# TLF01.net
KiCad netlist of a schematic drawn in EAGLE
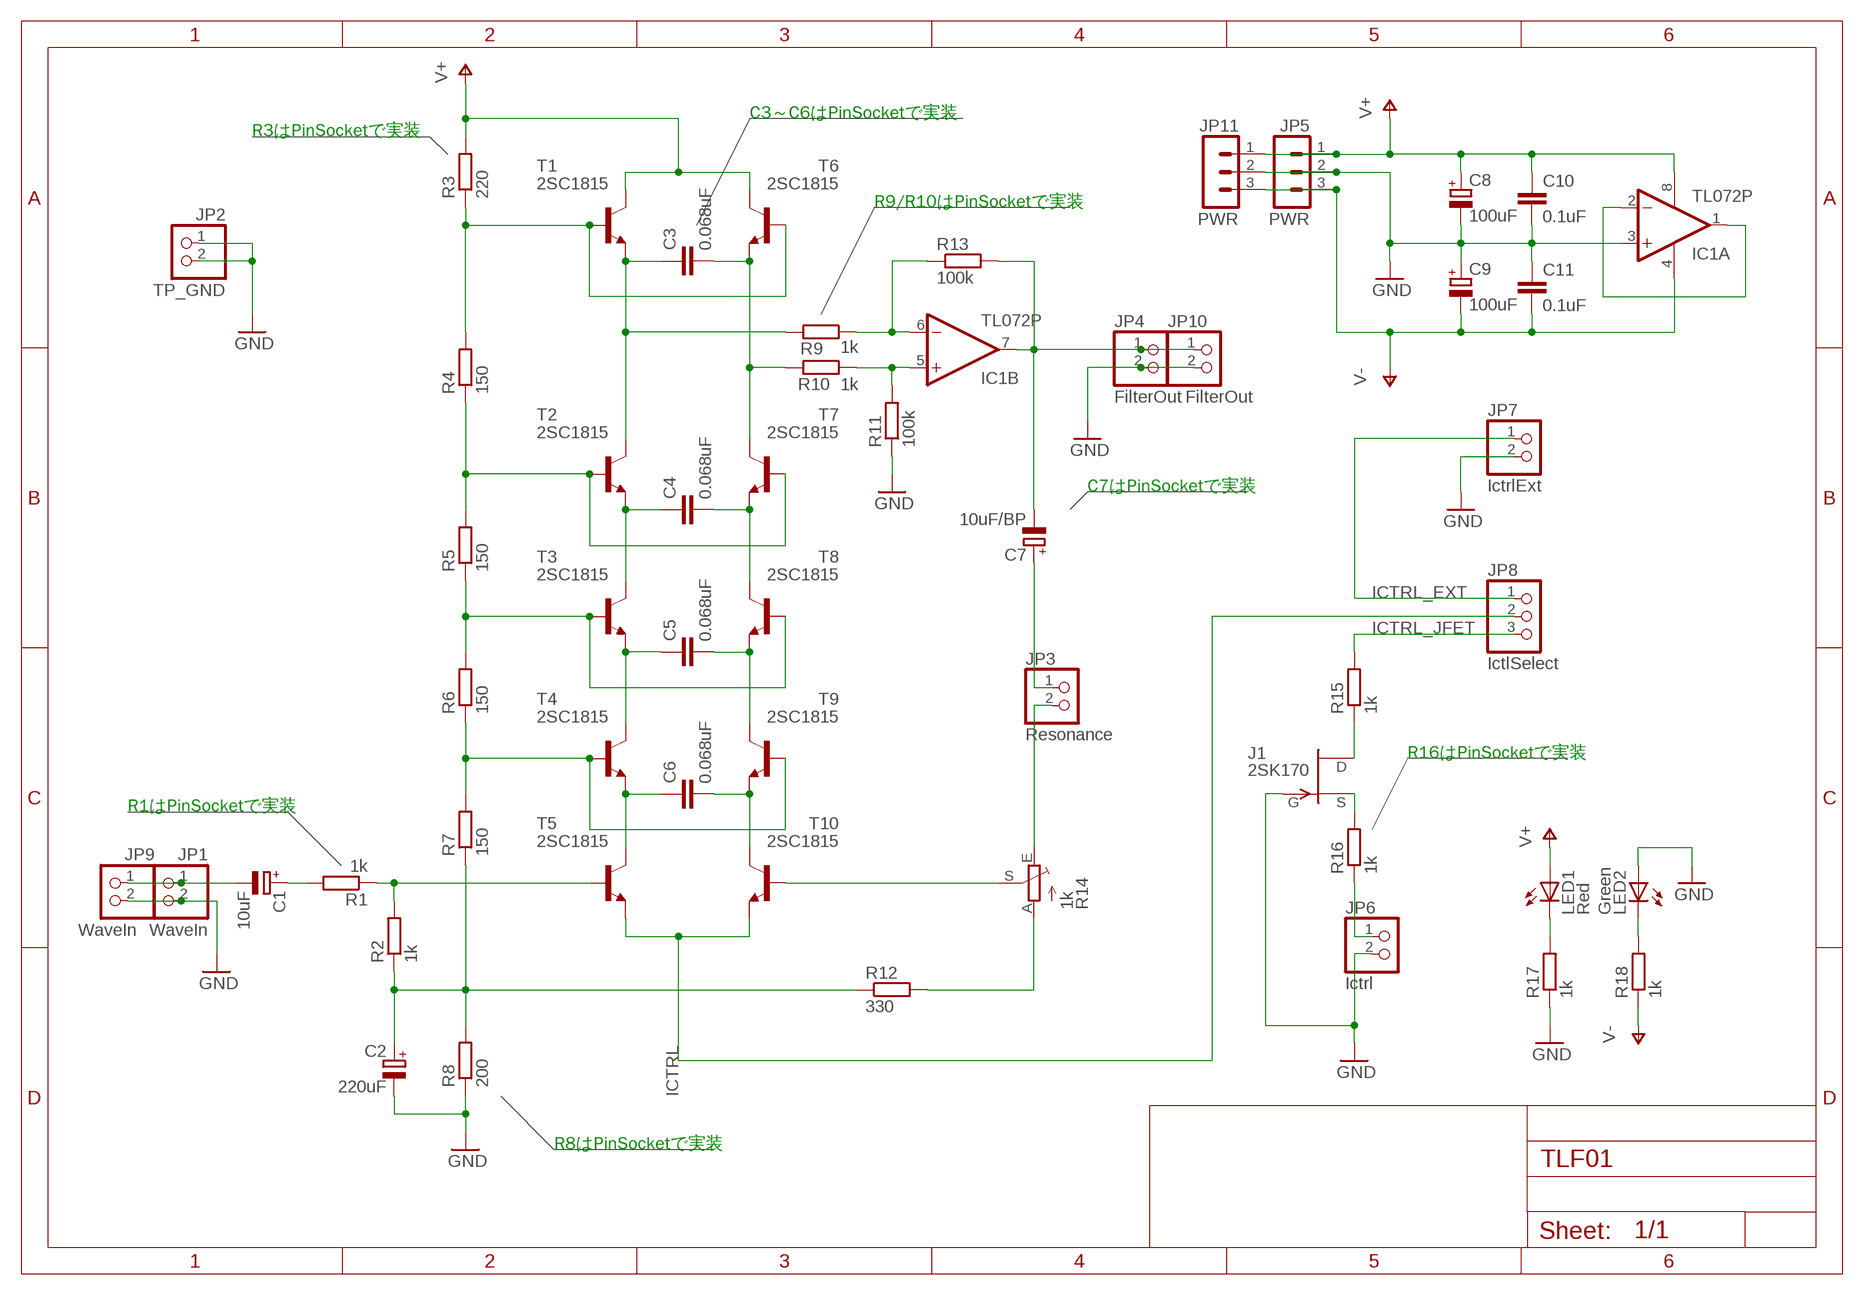
[diagram p0: schematic, sheet 1]

(export (version "E")
  (design (tool "Eeschema 10.0.6"))
  (components
    (comp (ref "C1")
      (value "10uF")
      (footprint "eagle-import:E2,5-6")
      (libsource (lib "eagle-import") (part "CPOL-EUE2.5-6"))
    )
    (comp (ref "C2")
      (value "220uF")
      (footprint "eagle-import:E5-8,5")
      (libsource (lib "eagle-import") (part "CPOL-EUE5-8.5"))
    )
    (comp (ref "C3")
      (value "0.068uF")
      (footprint "eagle-import:C075-052X106")
      (libsource (lib "eagle-import") (part "C-EU075-052X106"))
    )
    (comp (ref "C4")
      (value "0.068uF")
      (footprint "eagle-import:C075-052X106")
      (libsource (lib "eagle-import") (part "C-EU075-052X106"))
    )
    (comp (ref "C5")
      (value "0.068uF")
      (footprint "eagle-import:C075-052X106")
      (libsource (lib "eagle-import") (part "C-EU075-052X106"))
    )
    (comp (ref "C6")
      (value "0.068uF")
      (footprint "eagle-import:C075-052X106")
      (libsource (lib "eagle-import") (part "C-EU075-052X106"))
    )
    (comp (ref "C7")
      (value "10uF/BP")
      (footprint "eagle-import:E5-8,5")
      (libsource (lib "eagle-import") (part "CPOL-EUE5-8.5"))
    )
    (comp (ref "C8")
      (value "100uF")
      (footprint "eagle-import:E2,5-7")
      (libsource (lib "eagle-import") (part "CPOL-EUE2.5-7"))
    )
    (comp (ref "C9")
      (value "100uF")
      (footprint "eagle-import:E2,5-7")
      (libsource (lib "eagle-import") (part "CPOL-EUE2.5-7"))
    )
    (comp (ref "C10")
      (value "0.1uF")
      (footprint "eagle-import:C025-025X050")
      (libsource (lib "eagle-import") (part "C-EU025-025X050"))
    )
    (comp (ref "C11")
      (value "0.1uF")
      (footprint "eagle-import:C025-025X050")
      (libsource (lib "eagle-import") (part "C-EU025-025X050"))
    )
    (comp (ref "IC1")
      (value "TL072P")
      (footprint "eagle-import:DIL08")
      (libsource (lib "eagle-import") (part "TL072P"))
    )
    (comp (ref "J1")
      (value "2SK170")
      (footprint "eagle-import:TO-92")
      (libsource (lib "eagle-import") (part "2SK170"))
    )
    (comp (ref "JP1")
      (value "WaveIn")
      (footprint "eagle-import:1X02")
      (libsource (lib "eagle-import") (part "PINHD-1X2"))
    )
    (comp (ref "JP2")
      (value "TP_GND")
      (footprint "eagle-import:1X02")
      (libsource (lib "eagle-import") (part "PINHD-1X2"))
    )
    (comp (ref "JP3")
      (value "Resonance")
      (footprint "eagle-import:1X02")
      (libsource (lib "eagle-import") (part "PINHD-1X2"))
    )
    (comp (ref "JP4")
      (value "FilterOut")
      (footprint "eagle-import:1X02")
      (libsource (lib "eagle-import") (part "PINHD-1X2"))
    )
    (comp (ref "JP5")
      (value "PWR")
      (footprint "eagle-import:B3B-EH-A")
      (libsource (lib "eagle-import") (part "B3B-EH-A"))
    )
    (comp (ref "JP6")
      (value "Ictrl")
      (footprint "eagle-import:1X02")
      (libsource (lib "eagle-import") (part "PINHD-1X2"))
    )
    (comp (ref "JP7")
      (value "IctrlExt")
      (footprint "eagle-import:1X02")
      (libsource (lib "eagle-import") (part "PINHD-1X2"))
    )
    (comp (ref "JP8")
      (value "IctlSelect")
      (footprint "eagle-import:1X03")
      (libsource (lib "eagle-import") (part "PINHD-1X3"))
    )
    (comp (ref "JP9")
      (value "WaveIn")
      (footprint "eagle-import:1X02")
      (libsource (lib "eagle-import") (part "PINHD-1X2"))
    )
    (comp (ref "JP10")
      (value "FilterOut")
      (footprint "eagle-import:1X02")
      (libsource (lib "eagle-import") (part "PINHD-1X2"))
    )
    (comp (ref "JP11")
      (value "PWR")
      (footprint "eagle-import:B3B-EH-A")
      (libsource (lib "eagle-import") (part "B3B-EH-A"))
    )
    (comp (ref "LED1")
      (value "Red")
      (footprint "eagle-import:LED3MM")
      (libsource (lib "eagle-import") (part "LED3MM"))
    )
    (comp (ref "LED2")
      (value "Green")
      (footprint "eagle-import:LED3MM")
      (libsource (lib "eagle-import") (part "LED3MM"))
    )
    (comp (ref "R1")
      (value "1k")
      (footprint "eagle-import:0207_7")
      (libsource (lib "eagle-import") (part "R-EU_0207/7"))
    )
    (comp (ref "R2")
      (value "1k")
      (footprint "eagle-import:0207_7")
      (libsource (lib "eagle-import") (part "R-EU_0207/7"))
    )
    (comp (ref "R3")
      (value "220")
      (footprint "eagle-import:0207_7")
      (libsource (lib "eagle-import") (part "R-EU_0207/7"))
    )
    (comp (ref "R4")
      (value "150")
      (footprint "eagle-import:0207_7")
      (libsource (lib "eagle-import") (part "R-EU_0207/7"))
    )
    (comp (ref "R5")
      (value "150")
      (footprint "eagle-import:0207_7")
      (libsource (lib "eagle-import") (part "R-EU_0207/7"))
    )
    (comp (ref "R6")
      (value "150")
      (footprint "eagle-import:0207_7")
      (libsource (lib "eagle-import") (part "R-EU_0207/7"))
    )
    (comp (ref "R7")
      (value "150")
      (footprint "eagle-import:0207_7")
      (libsource (lib "eagle-import") (part "R-EU_0207/7"))
    )
    (comp (ref "R8")
      (value "200")
      (footprint "eagle-import:0207_7")
      (libsource (lib "eagle-import") (part "R-EU_0207/7"))
    )
    (comp (ref "R9")
      (value "1k")
      (footprint "eagle-import:0207_7")
      (libsource (lib "eagle-import") (part "R-EU_0207/7"))
    )
    (comp (ref "R10")
      (value "1k")
      (footprint "eagle-import:0207_7")
      (libsource (lib "eagle-import") (part "R-EU_0207/7"))
    )
    (comp (ref "R11")
      (value "100k")
      (footprint "eagle-import:0207_7")
      (libsource (lib "eagle-import") (part "R-EU_0207/7"))
    )
    (comp (ref "R12")
      (value "330")
      (footprint "eagle-import:0207_7")
      (libsource (lib "eagle-import") (part "R-EU_0207/7"))
    )
    (comp (ref "R13")
      (value "100k")
      (footprint "eagle-import:0207_7")
      (libsource (lib "eagle-import") (part "R-EU_0207/7"))
    )
    (comp (ref "R14")
      (value "1k")
      (footprint "eagle-import:B25P")
      (libsource (lib "eagle-import") (part "TRIM_EU-B25P"))
    )
    (comp (ref "R15")
      (value "1k")
      (footprint "eagle-import:0207_7")
      (libsource (lib "eagle-import") (part "R-EU_0207/7"))
    )
    (comp (ref "R16")
      (value "1k")
      (footprint "eagle-import:0207_7")
      (libsource (lib "eagle-import") (part "R-EU_0207/7"))
    )
    (comp (ref "R17")
      (value "1k")
      (footprint "eagle-import:0207_7")
      (libsource (lib "eagle-import") (part "R-EU_0207/7"))
    )
    (comp (ref "R18")
      (value "1k")
      (footprint "eagle-import:0207_7")
      (libsource (lib "eagle-import") (part "R-EU_0207/7"))
    )
    (comp (ref "T1")
      (value "2SC1815")
      (footprint "eagle-import:TO92-ECB")
      (libsource (lib "eagle-import") (part "-NPN-TO92-ECB"))
    )
    (comp (ref "T2")
      (value "2SC1815")
      (footprint "eagle-import:TO92-ECB")
      (libsource (lib "eagle-import") (part "-NPN-TO92-ECB"))
    )
    (comp (ref "T3")
      (value "2SC1815")
      (footprint "eagle-import:TO92-ECB")
      (libsource (lib "eagle-import") (part "-NPN-TO92-ECB"))
    )
    (comp (ref "T4")
      (value "2SC1815")
      (footprint "eagle-import:TO92-ECB")
      (libsource (lib "eagle-import") (part "-NPN-TO92-ECB"))
    )
    (comp (ref "T5")
      (value "2SC1815")
      (footprint "eagle-import:TO92-ECB")
      (libsource (lib "eagle-import") (part "-NPN-TO92-ECB"))
    )
    (comp (ref "T6")
      (value "2SC1815")
      (footprint "eagle-import:TO92-ECB")
      (libsource (lib "eagle-import") (part "-NPN-TO92-ECB"))
    )
    (comp (ref "T7")
      (value "2SC1815")
      (footprint "eagle-import:TO92-ECB")
      (libsource (lib "eagle-import") (part "-NPN-TO92-ECB"))
    )
    (comp (ref "T8")
      (value "2SC1815")
      (footprint "eagle-import:TO92-ECB")
      (libsource (lib "eagle-import") (part "-NPN-TO92-ECB"))
    )
    (comp (ref "T9")
      (value "2SC1815")
      (footprint "eagle-import:TO92-ECB")
      (libsource (lib "eagle-import") (part "-NPN-TO92-ECB"))
    )
    (comp (ref "T10")
      (value "2SC1815")
      (footprint "eagle-import:TO92-ECB")
      (libsource (lib "eagle-import") (part "-NPN-TO92-ECB"))
    )
  )
  (nets
    (net (code "1") (name "/ICTRL") (class "Default")
      (node (ref "JP8") (pin "2") (pinfunction "2_2") (pintype "passive"))
      (node (ref "T10") (pin "E") (pinfunction "E_E") (pintype "passive"))
      (node (ref "T5") (pin "E") (pinfunction "E_E") (pintype "passive"))
    )
    (net (code "2") (name "/ICTRL_EXT") (class "Default")
      (node (ref "JP7") (pin "1") (pinfunction "1_1") (pintype "passive"))
      (node (ref "JP8") (pin "1") (pinfunction "1_1") (pintype "passive"))
    )
    (net (code "3") (name "/ICTRL_JFET") (class "Default")
      (node (ref "JP8") (pin "3") (pinfunction "3_3") (pintype "passive"))
      (node (ref "R15") (pin "2") (pinfunction "2_2") (pintype "passive"))
    )
    (net (code "4") (name "GND") (class "Default")
      (node (ref "C10") (pin "2") (pinfunction "2_2") (pintype "passive"))
      (node (ref "C11") (pin "1") (pinfunction "1_1") (pintype "passive"))
      (node (ref "C2") (pin "-") (pinfunction "-_-") (pintype "passive"))
      (node (ref "C8") (pin "-") (pinfunction "-_-") (pintype "passive"))
      (node (ref "C9") (pin "+") (pinfunction "+_+") (pintype "passive"))
      (node (ref "IC1") (pin "3") (pinfunction "+IN_3") (pintype "input"))
      (node (ref "J1") (pin "2") (pinfunction "G_2") (pintype "passive"))
      (node (ref "JP1") (pin "2") (pinfunction "2_2") (pintype "passive"))
      (node (ref "JP10") (pin "2") (pinfunction "2_2") (pintype "passive"))
      (node (ref "JP11") (pin "2") (pinfunction "2_2") (pintype "passive"))
      (node (ref "JP2") (pin "1") (pinfunction "1_1") (pintype "passive"))
      (node (ref "JP2") (pin "2") (pinfunction "2_2") (pintype "passive"))
      (node (ref "JP4") (pin "2") (pinfunction "2_2") (pintype "passive"))
      (node (ref "JP5") (pin "2") (pinfunction "2_2") (pintype "passive"))
      (node (ref "JP6") (pin "2") (pinfunction "2_2") (pintype "passive"))
      (node (ref "JP7") (pin "2") (pinfunction "2_2") (pintype "passive"))
      (node (ref "JP9") (pin "2") (pinfunction "2_2") (pintype "passive"))
      (node (ref "LED2") (pin "A") (pinfunction "A_A") (pintype "passive"))
      (node (ref "R11") (pin "1") (pinfunction "1_1") (pintype "passive"))
      (node (ref "R17") (pin "1") (pinfunction "1_1") (pintype "passive"))
      (node (ref "R8") (pin "1") (pinfunction "1_1") (pintype "passive"))
    )
    (net (code "5") (name "Net-(C1-Pad+)") (class "Default")
      (node (ref "C1") (pin "+") (pinfunction "+_+") (pintype "passive"))
      (node (ref "R1") (pin "2") (pinfunction "2_2") (pintype "passive"))
    )
    (net (code "6") (name "Net-(C1-Pad-)") (class "Default")
      (node (ref "C1") (pin "-") (pinfunction "-_-") (pintype "passive"))
      (node (ref "JP1") (pin "1") (pinfunction "1_1") (pintype "passive"))
      (node (ref "JP9") (pin "1") (pinfunction "1_1") (pintype "passive"))
    )
    (net (code "7") (name "Net-(C2-Pad+)") (class "Default")
      (node (ref "C2") (pin "+") (pinfunction "+_+") (pintype "passive"))
      (node (ref "R12") (pin "1") (pinfunction "1_1") (pintype "passive"))
      (node (ref "R2") (pin "1") (pinfunction "1_1") (pintype "passive"))
      (node (ref "R7") (pin "1") (pinfunction "1_1") (pintype "passive"))
      (node (ref "R8") (pin "2") (pinfunction "2_2") (pintype "passive"))
    )
    (net (code "8") (name "Net-(C3-Pad1)") (class "Default")
      (node (ref "C3") (pin "1") (pinfunction "1_1") (pintype "passive"))
      (node (ref "R9") (pin "2") (pinfunction "2_2") (pintype "passive"))
      (node (ref "T1") (pin "E") (pinfunction "E_E") (pintype "passive"))
      (node (ref "T2") (pin "C") (pinfunction "C_C") (pintype "passive"))
    )
    (net (code "9") (name "Net-(C3-Pad2)") (class "Default")
      (node (ref "C3") (pin "2") (pinfunction "2_2") (pintype "passive"))
      (node (ref "R10") (pin "2") (pinfunction "2_2") (pintype "passive"))
      (node (ref "T6") (pin "E") (pinfunction "E_E") (pintype "passive"))
      (node (ref "T7") (pin "C") (pinfunction "C_C") (pintype "passive"))
    )
    (net (code "10") (name "Net-(C4-Pad1)") (class "Default")
      (node (ref "C4") (pin "1") (pinfunction "1_1") (pintype "passive"))
      (node (ref "T2") (pin "E") (pinfunction "E_E") (pintype "passive"))
      (node (ref "T3") (pin "C") (pinfunction "C_C") (pintype "passive"))
    )
    (net (code "11") (name "Net-(C4-Pad2)") (class "Default")
      (node (ref "C4") (pin "2") (pinfunction "2_2") (pintype "passive"))
      (node (ref "T7") (pin "E") (pinfunction "E_E") (pintype "passive"))
      (node (ref "T8") (pin "C") (pinfunction "C_C") (pintype "passive"))
    )
    (net (code "12") (name "Net-(C5-Pad1)") (class "Default")
      (node (ref "C5") (pin "1") (pinfunction "1_1") (pintype "passive"))
      (node (ref "T3") (pin "E") (pinfunction "E_E") (pintype "passive"))
      (node (ref "T4") (pin "C") (pinfunction "C_C") (pintype "passive"))
    )
    (net (code "13") (name "Net-(C5-Pad2)") (class "Default")
      (node (ref "C5") (pin "2") (pinfunction "2_2") (pintype "passive"))
      (node (ref "T8") (pin "E") (pinfunction "E_E") (pintype "passive"))
      (node (ref "T9") (pin "C") (pinfunction "C_C") (pintype "passive"))
    )
    (net (code "14") (name "Net-(C6-Pad1)") (class "Default")
      (node (ref "C6") (pin "1") (pinfunction "1_1") (pintype "passive"))
      (node (ref "T4") (pin "E") (pinfunction "E_E") (pintype "passive"))
      (node (ref "T5") (pin "C") (pinfunction "C_C") (pintype "passive"))
    )
    (net (code "15") (name "Net-(C6-Pad2)") (class "Default")
      (node (ref "C6") (pin "2") (pinfunction "2_2") (pintype "passive"))
      (node (ref "T10") (pin "C") (pinfunction "C_C") (pintype "passive"))
      (node (ref "T9") (pin "E") (pinfunction "E_E") (pintype "passive"))
    )
    (net (code "16") (name "Net-(C7-Pad+)") (class "Default")
      (node (ref "C7") (pin "+") (pinfunction "+_+") (pintype "passive"))
      (node (ref "JP3") (pin "1") (pinfunction "1_1") (pintype "passive"))
    )
    (net (code "17") (name "Net-(IC1A--IN)") (class "Default")
      (node (ref "IC1") (pin "1") (pinfunction "OUT_1") (pintype "output"))
      (node (ref "IC1") (pin "2") (pinfunction "-IN_2") (pintype "input"))
    )
    (net (code "18") (name "Net-(IC1B-+IN)") (class "Default")
      (node (ref "IC1") (pin "5") (pinfunction "+IN_5") (pintype "input"))
      (node (ref "R10") (pin "1") (pinfunction "1_1") (pintype "passive"))
      (node (ref "R11") (pin "2") (pinfunction "2_2") (pintype "passive"))
    )
    (net (code "19") (name "Net-(IC1B--IN)") (class "Default")
      (node (ref "IC1") (pin "6") (pinfunction "-IN_6") (pintype "input"))
      (node (ref "R13") (pin "1") (pinfunction "1_1") (pintype "passive"))
      (node (ref "R9") (pin "1") (pinfunction "1_1") (pintype "passive"))
    )
    (net (code "20") (name "Net-(IC1B-OUT)") (class "Default")
      (node (ref "C7") (pin "-") (pinfunction "-_-") (pintype "passive"))
      (node (ref "IC1") (pin "7") (pinfunction "OUT_7") (pintype "output"))
      (node (ref "JP10") (pin "1") (pinfunction "1_1") (pintype "passive"))
      (node (ref "JP4") (pin "1") (pinfunction "1_1") (pintype "passive"))
      (node (ref "R13") (pin "2") (pinfunction "2_2") (pintype "passive"))
    )
    (net (code "21") (name "Net-(J1-D)") (class "Default")
      (node (ref "J1") (pin "1") (pinfunction "D_1") (pintype "passive"))
      (node (ref "R15") (pin "1") (pinfunction "1_1") (pintype "passive"))
    )
    (net (code "22") (name "Net-(J1-S)") (class "Default")
      (node (ref "J1") (pin "3") (pinfunction "S_3") (pintype "passive"))
      (node (ref "R16") (pin "2") (pinfunction "2_2") (pintype "passive"))
    )
    (net (code "23") (name "Net-(JP3-Pad2)") (class "Default")
      (node (ref "JP3") (pin "2") (pinfunction "2_2") (pintype "passive"))
      (node (ref "R14") (pin "E") (pinfunction "E_E") (pintype "passive"))
    )
    (net (code "24") (name "Net-(JP6-Pad1)") (class "Default")
      (node (ref "JP6") (pin "1") (pinfunction "1_1") (pintype "passive"))
      (node (ref "R16") (pin "1") (pinfunction "1_1") (pintype "passive"))
    )
    (net (code "25") (name "Net-(LED1-C)") (class "Default")
      (node (ref "LED1") (pin "K") (pinfunction "C_K") (pintype "passive"))
      (node (ref "R17") (pin "2") (pinfunction "2_2") (pintype "passive"))
    )
    (net (code "26") (name "Net-(LED2-C)") (class "Default")
      (node (ref "LED2") (pin "K") (pinfunction "C_K") (pintype "passive"))
      (node (ref "R18") (pin "2") (pinfunction "2_2") (pintype "passive"))
    )
    (net (code "27") (name "Net-(R1-Pad1)") (class "Default")
      (node (ref "R1") (pin "1") (pinfunction "1_1") (pintype "passive"))
      (node (ref "R2") (pin "2") (pinfunction "2_2") (pintype "passive"))
      (node (ref "T5") (pin "B") (pinfunction "B_B") (pintype "passive"))
    )
    (net (code "28") (name "Net-(R3-Pad1)") (class "Default")
      (node (ref "R3") (pin "1") (pinfunction "1_1") (pintype "passive"))
      (node (ref "R4") (pin "2") (pinfunction "2_2") (pintype "passive"))
      (node (ref "T1") (pin "B") (pinfunction "B_B") (pintype "passive"))
      (node (ref "T6") (pin "B") (pinfunction "B_B") (pintype "passive"))
    )
    (net (code "29") (name "Net-(R4-Pad1)") (class "Default")
      (node (ref "R4") (pin "1") (pinfunction "1_1") (pintype "passive"))
      (node (ref "R5") (pin "2") (pinfunction "2_2") (pintype "passive"))
      (node (ref "T2") (pin "B") (pinfunction "B_B") (pintype "passive"))
      (node (ref "T7") (pin "B") (pinfunction "B_B") (pintype "passive"))
    )
    (net (code "30") (name "Net-(R5-Pad1)") (class "Default")
      (node (ref "R5") (pin "1") (pinfunction "1_1") (pintype "passive"))
      (node (ref "R6") (pin "2") (pinfunction "2_2") (pintype "passive"))
      (node (ref "T3") (pin "B") (pinfunction "B_B") (pintype "passive"))
      (node (ref "T8") (pin "B") (pinfunction "B_B") (pintype "passive"))
    )
    (net (code "31") (name "Net-(R6-Pad1)") (class "Default")
      (node (ref "R6") (pin "1") (pinfunction "1_1") (pintype "passive"))
      (node (ref "R7") (pin "2") (pinfunction "2_2") (pintype "passive"))
      (node (ref "T4") (pin "B") (pinfunction "B_B") (pintype "passive"))
      (node (ref "T9") (pin "B") (pinfunction "B_B") (pintype "passive"))
    )
    (net (code "32") (name "Net-(R12-Pad2)") (class "Default")
      (node (ref "R12") (pin "2") (pinfunction "2_2") (pintype "passive"))
      (node (ref "R14") (pin "A") (pinfunction "A_A") (pintype "passive"))
    )
    (net (code "33") (name "Net-(R14-PadS)") (class "Default")
      (node (ref "R14") (pin "S") (pinfunction "S_S") (pintype "passive"))
      (node (ref "T10") (pin "B") (pinfunction "B_B") (pintype "passive"))
    )
    (net (code "34") (name "V+") (class "Default")
      (node (ref "C10") (pin "1") (pinfunction "1_1") (pintype "passive"))
      (node (ref "C8") (pin "+") (pinfunction "+_+") (pintype "passive"))
      (node (ref "IC1") (pin "8") (pinfunction "V+_8") (pintype "power_in"))
      (node (ref "JP11") (pin "1") (pinfunction "1_1") (pintype "passive"))
      (node (ref "JP5") (pin "1") (pinfunction "1_1") (pintype "passive"))
      (node (ref "LED1") (pin "A") (pinfunction "A_A") (pintype "passive"))
      (node (ref "R3") (pin "2") (pinfunction "2_2") (pintype "passive"))
      (node (ref "T1") (pin "C") (pinfunction "C_C") (pintype "passive"))
      (node (ref "T6") (pin "C") (pinfunction "C_C") (pintype "passive"))
    )
    (net (code "35") (name "V-") (class "Default")
      (node (ref "C11") (pin "2") (pinfunction "2_2") (pintype "passive"))
      (node (ref "C9") (pin "-") (pinfunction "-_-") (pintype "passive"))
      (node (ref "IC1") (pin "4") (pinfunction "V-_4") (pintype "power_in"))
      (node (ref "JP11") (pin "3") (pinfunction "3_3") (pintype "passive"))
      (node (ref "JP5") (pin "3") (pinfunction "3_3") (pintype "passive"))
      (node (ref "R18") (pin "1") (pinfunction "1_1") (pintype "passive"))
    )
  )
)
